# design.net
KiCad netlist of a schematic drawn in Altium Designer
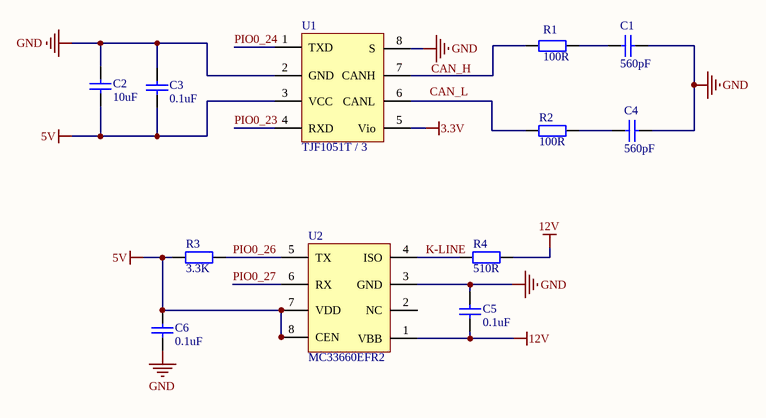
[diagram p0: 通信驱动电路.SchDoc]

(export (version "E")
  (design (tool "Eeschema 10.0.6"))
  (components
    (comp (ref "C1")
      (value "560pF")
      (footprint "0603")
      (description "ceramic")
      (libsource (lib "ToponLib") (part "Cap1"))
    )
    (comp (ref "C2")
      (value "10uF")
      (footprint "0603")
      (description "ceramic")
      (libsource (lib "ToponLib") (part "Cap1"))
    )
    (comp (ref "C3")
      (value "0.1uF")
      (footprint "0603")
      (description "ceramic")
      (libsource (lib "ToponLib") (part "Cap1"))
    )
    (comp (ref "C4")
      (value "560pF")
      (footprint "0603")
      (description "ceramic")
      (libsource (lib "ToponLib") (part "Cap1"))
    )
    (comp (ref "C5")
      (value "0.1uF")
      (footprint "0603")
      (description "ceramic")
      (libsource (lib "ToponLib") (part "Cap1"))
    )
    (comp (ref "C6")
      (value "0.1uF")
      (footprint "0603")
      (description "ceramic")
      (libsource (lib "ToponLib") (part "Cap1"))
    )
    (comp (ref "R1") (value "100R") (footprint "0603") (libsource (lib "ToponLib") (part "Res")))
    (comp (ref "R2") (value "100R") (footprint "0603") (libsource (lib "ToponLib") (part "Res")))
    (comp (ref "R3") (value "3.3K") (footprint "0603") (libsource (lib "ToponLib") (part "Res")))
    (comp (ref "R4") (value "510R") (footprint "0603") (libsource (lib "ToponLib") (part "Res")))
    (comp (ref "U1")
      (value "TJF1051T / 3")
      (footprint "TJF1051")
      (libsource (lib "ToponLib") (part "TJF1051T / 3"))
    )
    (comp (ref "U2")
      (value "MC33660EFR2")
      (footprint "SOP-8")
      (libsource (lib "ToponLib") (part "MC33660EFR2"))
    )
  )
  (nets
    (net (code "3") (name "/K-LINE") (class "Default")
      (node (ref "R4") (pin "2") (pinfunction "2_2") (pintype "passive"))
      (node (ref "U2") (pin "4") (pinfunction "ISO_4") (pintype "passive"))
    )
    (net (code "4") (name "/PIO0_23") (class "Default")
      (node (ref "U1") (pin "4") (pinfunction "RXD_4") (pintype "passive"))
    )
    (net (code "5") (name "/PIO0_24") (class "Default")
      (node (ref "U1") (pin "1") (pinfunction "TXD_1") (pintype "passive"))
    )
    (net (code "6") (name "/PIO0_26") (class "Default")
      (node (ref "R3") (pin "1") (pinfunction "1_1") (pintype "passive"))
      (node (ref "U2") (pin "5") (pinfunction "TX_5") (pintype "passive"))
    )
    (net (code "7") (name "/PIO0_27") (class "Default")
      (node (ref "U2") (pin "6") (pinfunction "RX_6") (pintype "passive"))
    )
    (net (code "8") (name "3.3V") (class "Default")
      (node (ref "U1") (pin "5") (pinfunction "Vio_5") (pintype "passive"))
    )
    (net (code "9") (name "5V") (class "Default")
      (node (ref "C2") (pin "1") (pinfunction "1_1") (pintype "passive"))
      (node (ref "C3") (pin "1") (pinfunction "1_1") (pintype "passive"))
      (node (ref "C6") (pin "2") (pinfunction "2_2") (pintype "passive"))
      (node (ref "R3") (pin "2") (pinfunction "2_2") (pintype "passive"))
      (node (ref "U1") (pin "3") (pinfunction "VCC_3") (pintype "passive"))
      (node (ref "U2") (pin "7") (pinfunction "VDD_7") (pintype "passive"))
      (node (ref "U2") (pin "8") (pinfunction "CEN_8") (pintype "passive"))
    )
    (net (code "10") (name "12V") (class "Default")
      (node (ref "C5") (pin "1") (pinfunction "1_1") (pintype "passive"))
      (node (ref "R4") (pin "1") (pinfunction "1_1") (pintype "passive"))
      (node (ref "U2") (pin "1") (pinfunction "VBB_1") (pintype "passive"))
    )
    (net (code "11") (name "GND") (class "Default")
      (node (ref "C1") (pin "1") (pinfunction "1_1") (pintype "passive"))
      (node (ref "C2") (pin "2") (pinfunction "2_2") (pintype "passive"))
      (node (ref "C3") (pin "2") (pinfunction "2_2") (pintype "passive"))
      (node (ref "C4") (pin "1") (pinfunction "1_1") (pintype "passive"))
      (node (ref "C5") (pin "2") (pinfunction "2_2") (pintype "passive"))
      (node (ref "C6") (pin "1") (pinfunction "1_1") (pintype "passive"))
      (node (ref "U1") (pin "2") (pinfunction "GND_2") (pintype "passive"))
      (node (ref "U1") (pin "8") (pinfunction "S_8") (pintype "passive"))
      (node (ref "U2") (pin "3") (pinfunction "GND_3") (pintype "passive"))
    )
    (net (code "12") (name "Net-(C1-Pad2)") (class "Default")
      (node (ref "C1") (pin "2") (pinfunction "2_2") (pintype "passive"))
      (node (ref "R1") (pin "1") (pinfunction "1_1") (pintype "passive"))
    )
    (net (code "13") (name "Net-(C4-Pad2)") (class "Default")
      (node (ref "C4") (pin "2") (pinfunction "2_2") (pintype "passive"))
      (node (ref "R2") (pin "1") (pinfunction "1_1") (pintype "passive"))
    )
    (net (code "14") (name "Net-(U1-CANH)") (class "Default")
      (node (ref "R1") (pin "2") (pinfunction "2_2") (pintype "passive"))
      (node (ref "U1") (pin "7") (pinfunction "CANH_7") (pintype "passive"))
    )
    (net (code "15") (name "Net-(U1-CANL)") (class "Default")
      (node (ref "R2") (pin "2") (pinfunction "2_2") (pintype "passive"))
      (node (ref "U1") (pin "6") (pinfunction "CANL_6") (pintype "passive"))
    )
    (net (code "16") (name "unconnected-(U2-NC-Pad2)") (class "Default")
      (node (ref "U2") (pin "2") (pinfunction "NC_2") (pintype "passive"))
    )
  )
)
